# midi2cv.net
KiCad netlist of a schematic drawn in EAGLE
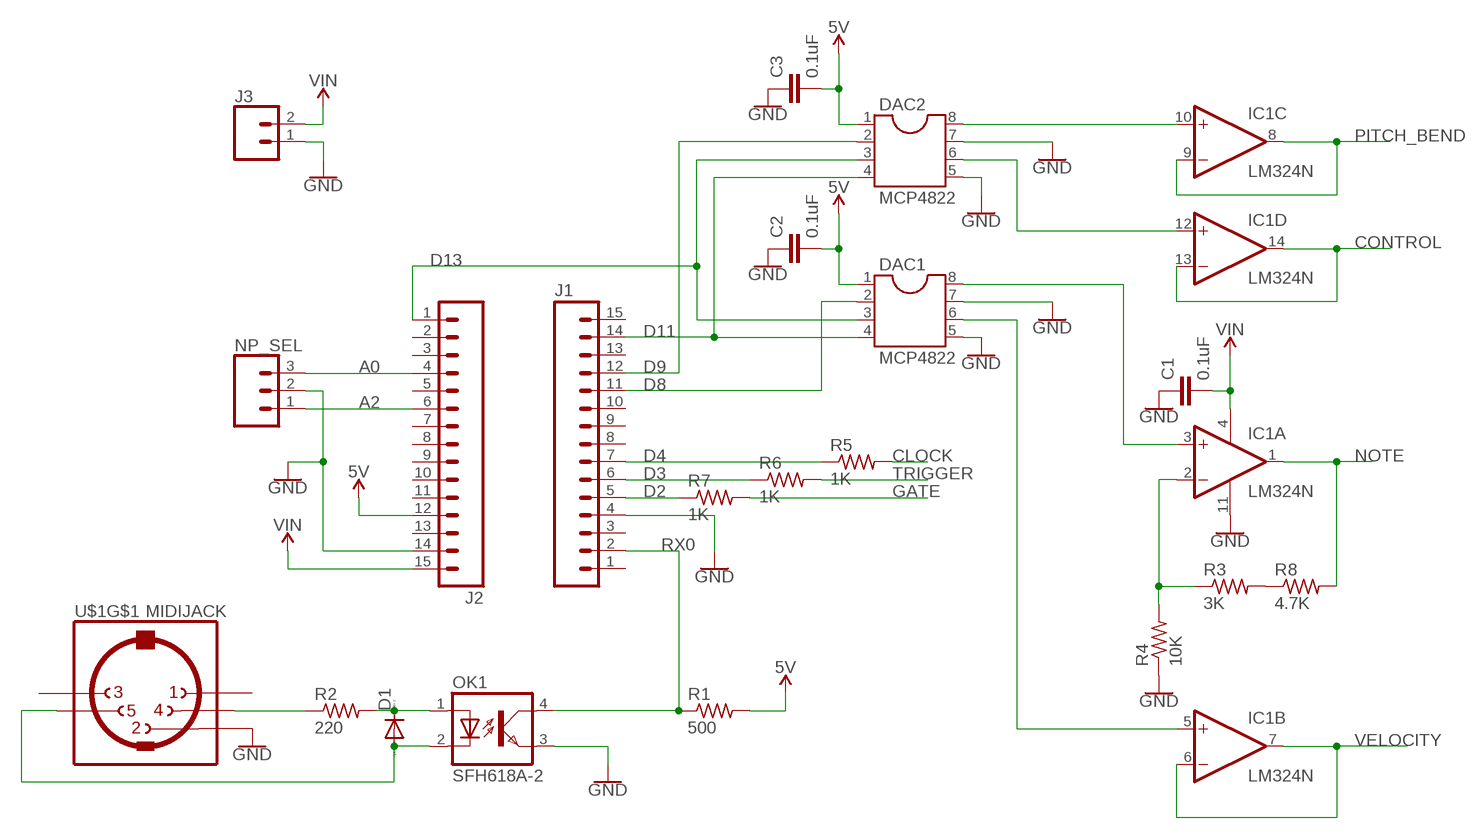
[diagram p0: schematic, sheet 1]

(export (version "E")
  (design (tool "Eeschema 10.0.6"))
  (components
    (comp (ref "C1")
      (value "0.1uF")
      (footprint "eagle-import:CAP-PTH-SMALL-KIT")
      (libsource (lib "eagle-import") (part "0.1UF-KIT-EZ-50V-20%"))
    )
    (comp (ref "C2")
      (value "0.1uF")
      (footprint "eagle-import:CAP-PTH-SMALL-KIT")
      (libsource (lib "eagle-import") (part "0.1UF-KIT-EZ-50V-20%"))
    )
    (comp (ref "C3")
      (value "0.1uF")
      (footprint "eagle-import:CAP-PTH-SMALL-KIT")
      (libsource (lib "eagle-import") (part "0.1UF-KIT-EZ-50V-20%"))
    )
    (comp (ref "D1")
      (value "DIODE-D-10")
      (footprint "eagle-import:D-10")
      (libsource (lib "eagle-import") (part "DIODE-D-10"))
    )
    (comp (ref "DAC1")
      (value "MCP4822")
      (footprint "eagle-import:SOCKET-08")
      (libsource (lib "eagle-import") (part "DIL8S"))
    )
    (comp (ref "DAC2")
      (value "MCP4822")
      (footprint "eagle-import:SOCKET-08")
      (libsource (lib "eagle-import") (part "DIL8S"))
    )
    (comp (ref "IC1")
      (value "LM324N")
      (footprint "eagle-import:DIL14")
      (libsource (lib "eagle-import") (part "LM324N"))
    )
    (comp (ref "J1")
      (value "M15")
      (footprint "eagle-import:1X15")
      (libsource (lib "eagle-import") (part "M15"))
    )
    (comp (ref "J2")
      (value "M15")
      (footprint "eagle-import:1X15")
      (libsource (lib "eagle-import") (part "M15"))
    )
    (comp (ref "J3")
      (value "CONN_025MM")
      (footprint "eagle-import:SCREWTERMINAL-5MM-2")
      (libsource (lib "eagle-import") (part "CONN_025MM"))
    )
    (comp (ref "NP_SEL")
      (value "CONN_03")
      (footprint "eagle-import:1X03")
      (libsource (lib "eagle-import") (part "CONN_03"))
    )
    (comp (ref "OK1")
      (value "SFH618A-2")
      (footprint "eagle-import:DIP4")
      (fields (field (name "MF") "VISHAY/TELEFUNKEN"))
      (libsource (lib "eagle-import") (part "SFH618?A-2"))
    )
    (comp (ref "R1")
      (value "500")
      (footprint "eagle-import:0207_10")
      (libsource (lib "eagle-import") (part "R-US_0207/10"))
    )
    (comp (ref "R2")
      (value "220")
      (footprint "eagle-import:0207_10")
      (libsource (lib "eagle-import") (part "R-US_0207/10"))
    )
    (comp (ref "R3")
      (value "3K")
      (footprint "eagle-import:0207_10")
      (libsource (lib "eagle-import") (part "R-US_0207/10"))
    )
    (comp (ref "R4")
      (value "10K")
      (footprint "eagle-import:0207_10")
      (libsource (lib "eagle-import") (part "R-US_0207/10"))
    )
    (comp (ref "R5")
      (value "1K")
      (footprint "eagle-import:0207_10")
      (libsource (lib "eagle-import") (part "R-US_0207/10"))
    )
    (comp (ref "R6")
      (value "1K")
      (footprint "eagle-import:0207_10")
      (libsource (lib "eagle-import") (part "R-US_0207/10"))
    )
    (comp (ref "R7")
      (value "1K")
      (footprint "eagle-import:0207_10")
      (libsource (lib "eagle-import") (part "R-US_0207/10"))
    )
    (comp (ref "R8")
      (value "4.7K")
      (footprint "eagle-import:0207_10")
      (libsource (lib "eagle-import") (part "R-US_0207/10"))
    )
    (comp (ref "U$1")
      (value "MIDIJACK")
      (footprint "eagle-import:CP-2350")
      (libsource (lib "eagle-import") (part "MIDIJACK"))
    )
  )
  (nets
    (net (code "1") (name "/A0") (class "Default")
      (node (ref "J2") (pin "4") (pinfunction "4_4") (pintype "passive"))
      (node (ref "NP_SEL") (pin "3") (pinfunction "3_3") (pintype "passive"))
    )
    (net (code "2") (name "/A2") (class "Default")
      (node (ref "J2") (pin "6") (pinfunction "6_6") (pintype "passive"))
      (node (ref "NP_SEL") (pin "1") (pinfunction "1_1") (pintype "passive"))
    )
    (net (code "3") (name "/CLOCK") (class "Default")
      (node (ref "R5") (pin "2") (pinfunction "2_2") (pintype "passive"))
    )
    (net (code "4") (name "/CONTROL") (class "Default")
      (node (ref "IC1") (pin "13") (pinfunction "-IN_13") (pintype "input"))
      (node (ref "IC1") (pin "14") (pinfunction "OUT_14") (pintype "output"))
    )
    (net (code "5") (name "/D2") (class "Default")
      (node (ref "J1") (pin "5") (pinfunction "5_5") (pintype "passive"))
      (node (ref "R7") (pin "1") (pinfunction "1_1") (pintype "passive"))
    )
    (net (code "6") (name "/D3") (class "Default")
      (node (ref "J1") (pin "6") (pinfunction "6_6") (pintype "passive"))
      (node (ref "R6") (pin "1") (pinfunction "1_1") (pintype "passive"))
    )
    (net (code "7") (name "/D4") (class "Default")
      (node (ref "J1") (pin "7") (pinfunction "7_7") (pintype "passive"))
      (node (ref "R5") (pin "1") (pinfunction "1_1") (pintype "passive"))
    )
    (net (code "8") (name "/D8") (class "Default")
      (node (ref "DAC1") (pin "2") (pinfunction "2_2") (pintype "passive"))
      (node (ref "J1") (pin "11") (pinfunction "11_11") (pintype "passive"))
    )
    (net (code "9") (name "/D9") (class "Default")
      (node (ref "DAC2") (pin "2") (pinfunction "2_2") (pintype "passive"))
      (node (ref "J1") (pin "12") (pinfunction "12_12") (pintype "passive"))
    )
    (net (code "10") (name "/D11") (class "Default")
      (node (ref "DAC1") (pin "4") (pinfunction "4_4") (pintype "passive"))
      (node (ref "DAC2") (pin "4") (pinfunction "4_4") (pintype "passive"))
      (node (ref "J1") (pin "14") (pinfunction "14_14") (pintype "passive"))
    )
    (net (code "11") (name "/D13") (class "Default")
      (node (ref "DAC1") (pin "3") (pinfunction "3_3") (pintype "passive"))
      (node (ref "DAC2") (pin "3") (pinfunction "3_3") (pintype "passive"))
      (node (ref "J2") (pin "1") (pinfunction "1_1") (pintype "passive"))
    )
    (net (code "12") (name "/GATE") (class "Default")
      (node (ref "R7") (pin "2") (pinfunction "2_2") (pintype "passive"))
    )
    (net (code "13") (name "/NOTE") (class "Default")
      (node (ref "IC1") (pin "1") (pinfunction "OUT_1") (pintype "output"))
      (node (ref "R8") (pin "2") (pinfunction "2_2") (pintype "passive"))
    )
    (net (code "14") (name "/PITCH_BEND") (class "Default")
      (node (ref "IC1") (pin "8") (pinfunction "OUT_8") (pintype "output"))
      (node (ref "IC1") (pin "9") (pinfunction "-IN_9") (pintype "input"))
    )
    (net (code "15") (name "/RX0") (class "Default")
      (node (ref "J1") (pin "2") (pinfunction "2_2") (pintype "passive"))
      (node (ref "OK1") (pin "4") (pinfunction "COL_4") (pintype "passive"))
      (node (ref "R1") (pin "1") (pinfunction "1_1") (pintype "passive"))
    )
    (net (code "16") (name "/TRIGGER") (class "Default")
      (node (ref "R6") (pin "2") (pinfunction "2_2") (pintype "passive"))
    )
    (net (code "17") (name "/VELOCITY") (class "Default")
      (node (ref "IC1") (pin "6") (pinfunction "-IN_6") (pintype "input"))
      (node (ref "IC1") (pin "7") (pinfunction "OUT_7") (pintype "output"))
    )
    (net (code "18") (name "5V") (class "Default")
      (node (ref "C2") (pin "2") (pinfunction "2_2") (pintype "passive"))
      (node (ref "C3") (pin "2") (pinfunction "2_2") (pintype "passive"))
      (node (ref "DAC1") (pin "1") (pinfunction "1_1") (pintype "passive"))
      (node (ref "DAC2") (pin "1") (pinfunction "1_1") (pintype "passive"))
      (node (ref "J2") (pin "12") (pinfunction "12_12") (pintype "passive"))
      (node (ref "R1") (pin "2") (pinfunction "2_2") (pintype "passive"))
    )
    (net (code "19") (name "GND") (class "Default")
      (node (ref "C1") (pin "1") (pinfunction "1_1") (pintype "passive"))
      (node (ref "C2") (pin "1") (pinfunction "1_1") (pintype "passive"))
      (node (ref "C3") (pin "1") (pinfunction "1_1") (pintype "passive"))
      (node (ref "DAC1") (pin "5") (pinfunction "5_5") (pintype "passive"))
      (node (ref "DAC1") (pin "7") (pinfunction "7_7") (pintype "passive"))
      (node (ref "DAC2") (pin "5") (pinfunction "5_5") (pintype "passive"))
      (node (ref "DAC2") (pin "7") (pinfunction "7_7") (pintype "passive"))
      (node (ref "IC1") (pin "11") (pinfunction "V-_11") (pintype "power_in"))
      (node (ref "J1") (pin "4") (pinfunction "4_4") (pintype "passive"))
      (node (ref "J2") (pin "14") (pinfunction "14_14") (pintype "passive"))
      (node (ref "J3") (pin "1") (pinfunction "1_1") (pintype "passive"))
      (node (ref "NP_SEL") (pin "2") (pinfunction "2_2") (pintype "passive"))
      (node (ref "OK1") (pin "3") (pinfunction "EMIT_3") (pintype "passive"))
      (node (ref "R4") (pin "1") (pinfunction "1_1") (pintype "passive"))
      (node (ref "U$1") (pin "2") (pinfunction "2_2") (pintype "passive"))
    )
    (net (code "20") (name "Net-(IC1A-+IN)") (class "Default")
      (node (ref "DAC1") (pin "8") (pinfunction "8_8") (pintype "passive"))
      (node (ref "IC1") (pin "3") (pinfunction "+IN_3") (pintype "input"))
    )
    (net (code "21") (name "Net-(IC1A--IN)") (class "Default")
      (node (ref "IC1") (pin "2") (pinfunction "-IN_2") (pintype "input"))
      (node (ref "R3") (pin "1") (pinfunction "1_1") (pintype "passive"))
      (node (ref "R4") (pin "2") (pinfunction "2_2") (pintype "passive"))
    )
    (net (code "22") (name "Net-(IC1B-+IN)") (class "Default")
      (node (ref "DAC1") (pin "6") (pinfunction "6_6") (pintype "passive"))
      (node (ref "IC1") (pin "5") (pinfunction "+IN_5") (pintype "input"))
    )
    (net (code "23") (name "Net-(IC1C-+IN)") (class "Default")
      (node (ref "DAC2") (pin "8") (pinfunction "8_8") (pintype "passive"))
      (node (ref "IC1") (pin "10") (pinfunction "+IN_10") (pintype "input"))
    )
    (net (code "24") (name "Net-(IC1D-+IN)") (class "Default")
      (node (ref "DAC2") (pin "6") (pinfunction "6_6") (pintype "passive"))
      (node (ref "IC1") (pin "12") (pinfunction "+IN_12") (pintype "input"))
    )
    (net (code "25") (name "Net-(OK1-A)") (class "Default")
      (node (ref "D1") (pin "C") (pinfunction "C_C") (pintype "passive"))
      (node (ref "OK1") (pin "1") (pinfunction "A_1") (pintype "passive"))
      (node (ref "R2") (pin "2") (pinfunction "2_2") (pintype "passive"))
    )
    (net (code "26") (name "Net-(OK1-C)") (class "Default")
      (node (ref "D1") (pin "A") (pinfunction "A_A") (pintype "passive"))
      (node (ref "OK1") (pin "2") (pinfunction "C_2") (pintype "passive"))
      (node (ref "U$1") (pin "5") (pinfunction "5_5") (pintype "passive"))
    )
    (net (code "27") (name "Net-(R2-Pad1)") (class "Default")
      (node (ref "R2") (pin "1") (pinfunction "1_1") (pintype "passive"))
      (node (ref "U$1") (pin "4") (pinfunction "4_4") (pintype "passive"))
    )
    (net (code "28") (name "Net-(R3-Pad2)") (class "Default")
      (node (ref "R3") (pin "2") (pinfunction "2_2") (pintype "passive"))
      (node (ref "R8") (pin "1") (pinfunction "1_1") (pintype "passive"))
    )
    (net (code "29") (name "VIN") (class "Default")
      (node (ref "C1") (pin "2") (pinfunction "2_2") (pintype "passive"))
      (node (ref "IC1") (pin "4") (pinfunction "V+_4") (pintype "power_in"))
      (node (ref "J2") (pin "15") (pinfunction "15_15") (pintype "passive"))
      (node (ref "J3") (pin "2") (pinfunction "2_2") (pintype "passive"))
    )
    (net (code "30") (name "unconnected-(J1-Pad1)") (class "Default")
      (node (ref "J1") (pin "1") (pinfunction "1_1") (pintype "passive"))
    )
    (net (code "31") (name "unconnected-(J1-Pad3)") (class "Default")
      (node (ref "J1") (pin "3") (pinfunction "3_3") (pintype "passive"))
    )
    (net (code "32") (name "unconnected-(J1-Pad8)") (class "Default")
      (node (ref "J1") (pin "8") (pinfunction "8_8") (pintype "passive"))
    )
    (net (code "33") (name "unconnected-(J1-Pad9)") (class "Default")
      (node (ref "J1") (pin "9") (pinfunction "9_9") (pintype "passive"))
    )
    (net (code "34") (name "unconnected-(J1-Pad10)") (class "Default")
      (node (ref "J1") (pin "10") (pinfunction "10_10") (pintype "passive"))
    )
    (net (code "35") (name "unconnected-(J1-Pad13)") (class "Default")
      (node (ref "J1") (pin "13") (pinfunction "13_13") (pintype "passive"))
    )
    (net (code "36") (name "unconnected-(J1-Pad15)") (class "Default")
      (node (ref "J1") (pin "15") (pinfunction "15_15") (pintype "passive"))
    )
    (net (code "37") (name "unconnected-(J2-Pad2)") (class "Default")
      (node (ref "J2") (pin "2") (pinfunction "2_2") (pintype "passive"))
    )
    (net (code "38") (name "unconnected-(J2-Pad3)") (class "Default")
      (node (ref "J2") (pin "3") (pinfunction "3_3") (pintype "passive"))
    )
    (net (code "39") (name "unconnected-(J2-Pad5)") (class "Default")
      (node (ref "J2") (pin "5") (pinfunction "5_5") (pintype "passive"))
    )
    (net (code "40") (name "unconnected-(J2-Pad7)") (class "Default")
      (node (ref "J2") (pin "7") (pinfunction "7_7") (pintype "passive"))
    )
    (net (code "41") (name "unconnected-(J2-Pad8)") (class "Default")
      (node (ref "J2") (pin "8") (pinfunction "8_8") (pintype "passive"))
    )
    (net (code "42") (name "unconnected-(J2-Pad9)") (class "Default")
      (node (ref "J2") (pin "9") (pinfunction "9_9") (pintype "passive"))
    )
    (net (code "43") (name "unconnected-(J2-Pad10)") (class "Default")
      (node (ref "J2") (pin "10") (pinfunction "10_10") (pintype "passive"))
    )
    (net (code "44") (name "unconnected-(J2-Pad11)") (class "Default")
      (node (ref "J2") (pin "11") (pinfunction "11_11") (pintype "passive"))
    )
    (net (code "45") (name "unconnected-(J2-Pad13)") (class "Default")
      (node (ref "J2") (pin "13") (pinfunction "13_13") (pintype "passive"))
    )
    (net (code "46") (name "unconnected-(U$1-Pad1)") (class "Default")
      (node (ref "U$1") (pin "1") (pinfunction "1_1") (pintype "passive"))
    )
    (net (code "47") (name "unconnected-(U$1-Pad3)") (class "Default")
      (node (ref "U$1") (pin "3") (pinfunction "3_3") (pintype "passive"))
    )
  )
)
